# USB.net
KiCad netlist of a schematic drawn in Altium Designer
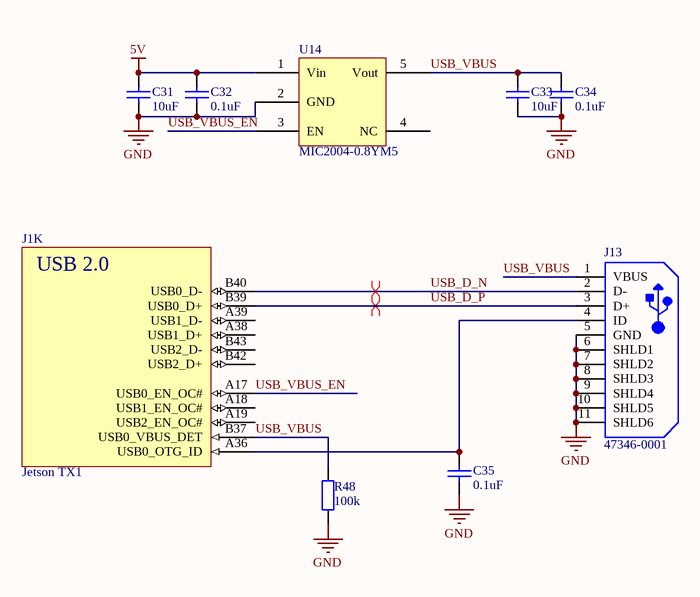
[diagram p0: USB.SchDoc]

(export (version "E")
  (design (tool "Eeschema 10.0.6"))
  (components
    (comp (ref "C31")
      (value "10uF")
      (footprint "0603C_M")
      (description "CAP CER 10UF 6.3V X5R 0603")
      (fields
        (field (name "MANUFACTURER") "Murata Electronics North America")
        (field (name "MANUFACTURER PART NUMBER") "GRM188R60J106ME47D")
      )
      (libsource (lib "KMTI-main") (part "GRM188R60J106ME47D"))
    )
    (comp (ref "C32")
      (value "GRM155R71C104KA88D")
      (footprint "0402C_M")
      (description "CAP CER 0.1UF 16V X7R 0402")
      (fields
        (field (name "MANUFACTURER") "Murata Electronics North America")
        (field (name "TOLERANCE") "±10%")
        (field (name "CAPACITANCE") "0.1uF")
      )
      (libsource (lib "KMTI-main") (part "GRM155R71C104KA88D"))
    )
    (comp (ref "C33")
      (value "10uF")
      (footprint "0603C_M")
      (description "CAP CER 10UF 6.3V X5R 0603")
      (fields
        (field (name "MANUFACTURER") "Murata Electronics North America")
        (field (name "MANUFACTURER PART NUMBER") "GRM188R60J106ME47D")
      )
      (libsource (lib "KMTI-main") (part "GRM188R60J106ME47D"))
    )
    (comp (ref "C34")
      (value "GRM155R71C104KA88D")
      (footprint "0402C_M")
      (description "CAP CER 0.1UF 16V X7R 0402")
      (fields
        (field (name "MANUFACTURER") "Murata Electronics North America")
        (field (name "TOLERANCE") "±10%")
        (field (name "CAPACITANCE") "0.1uF")
      )
      (libsource (lib "KMTI-main") (part "GRM155R71C104KA88D"))
    )
    (comp (ref "C35")
      (value "GRM155R71C104KA88D")
      (footprint "0402C_M")
      (description "CAP CER 0.1UF 16V X7R 0402")
      (fields
        (field (name "MANUFACTURER") "Murata Electronics North America")
        (field (name "TOLERANCE") "±10%")
        (field (name "CAPACITANCE") "0.1uF")
      )
      (libsource (lib "KMTI-main") (part "GRM155R71C104KA88D"))
    )
    (comp (ref "J1")
      (value "Jetson TX1")
      (footprint "Nvidia Jetson TX1")
      (description "Nvidia computing module")
      (libsource (lib "Modules") (part "NVIDIA_Jetson_TX1"))
    )
    (comp (ref "J13")
      (value "47346-0001")
      (footprint "MOLX-47346-0001-5_V")
      (description "Micro-USB B Receptacle with Flange, -30 to 85 degC, 5-Pin SMD, RoHS, Tape and Reel")
      (fields (field (name "MANUFACTURER") "Molex"))
      (libsource (lib "Altium Content Vault") (part "MOLX-47346-0001-5"))
    )
    (comp (ref "R48")
      (value "CRCW0402100KJNED")
      (footprint "0402R_M")
      (description "RES SMD 100K OHM 5% 1/16W 0402")
      (fields
        (field (name "MANUFACTURER") "Vishay")
        (field (name "TOLERANCE") "5 %")
        (field (name "RESISTANCE") "100k")
      )
      (libsource (lib "KMTI-main") (part "CRCW0402100KJNED"))
    )
    (comp (ref "U14")
      (value "MIC2004-0.8YM5")
      (footprint "SOT23_M5_L")
      (description "IC DISTRIBUTION SW 0.8A SOT23-5")
      (fields (field (name "MANUFACTURER") "Microchip Technology"))
      (libsource (lib "KMTI-main") (part "MIC2004-0.8YM5"))
    )
  )
  (nets
    (net (code "1") (name "/USB_D_N") (class "Default")
      (node (ref "J1") (pin "B40") (pinfunction "USB0_D-_B40") (pintype "bidirectional"))
      (node (ref "J13") (pin "2") (pinfunction "D-_2") (pintype "passive"))
    )
    (net (code "2") (name "/USB_D_P") (class "Default")
      (node (ref "J1") (pin "B39") (pinfunction "USB0_D+_B39") (pintype "bidirectional"))
      (node (ref "J13") (pin "3") (pinfunction "D+_3") (pintype "passive"))
    )
    (net (code "3") (name "/USB_VBUS") (class "Default")
      (node (ref "C33") (pin "2") (pinfunction "2_2") (pintype "passive"))
      (node (ref "C34") (pin "2") (pinfunction "2_2") (pintype "passive"))
      (node (ref "J1") (pin "B37") (pinfunction "USB0_VBUS_DET_B37") (pintype "input"))
      (node (ref "J13") (pin "1") (pinfunction "VBUS_1") (pintype "passive"))
      (node (ref "R48") (pin "2") (pinfunction "2_2") (pintype "passive"))
      (node (ref "U14") (pin "5") (pinfunction "Vout_5") (pintype "passive"))
    )
    (net (code "4") (name "/USB_VBUS_EN") (class "Default")
      (node (ref "J1") (pin "A17") (pinfunction "USB0_EN_OC#_A17") (pintype "bidirectional"))
      (node (ref "U14") (pin "3") (pinfunction "EN_3") (pintype "passive"))
    )
    (net (code "5") (name "5V") (class "Default")
      (node (ref "C31") (pin "2") (pinfunction "2_2") (pintype "passive"))
      (node (ref "C32") (pin "2") (pinfunction "2_2") (pintype "passive"))
      (node (ref "U14") (pin "1") (pinfunction "Vin_1") (pintype "passive"))
    )
    (net (code "6") (name "GND") (class "Default")
      (node (ref "C31") (pin "1") (pinfunction "1_1") (pintype "passive"))
      (node (ref "C32") (pin "1") (pinfunction "1_1") (pintype "passive"))
      (node (ref "C33") (pin "1") (pinfunction "1_1") (pintype "passive"))
      (node (ref "C34") (pin "1") (pinfunction "1_1") (pintype "passive"))
      (node (ref "C35") (pin "1") (pinfunction "1_1") (pintype "passive"))
      (node (ref "J13") (pin "10") (pinfunction "SHLD5_10") (pintype "passive"))
      (node (ref "J13") (pin "11") (pinfunction "SHLD6_11") (pintype "passive"))
      (node (ref "J13") (pin "5") (pinfunction "GND_5") (pintype "passive"))
      (node (ref "J13") (pin "6") (pinfunction "SHLD1_6") (pintype "passive"))
      (node (ref "J13") (pin "7") (pinfunction "SHLD2_7") (pintype "passive"))
      (node (ref "J13") (pin "8") (pinfunction "SHLD3_8") (pintype "passive"))
      (node (ref "J13") (pin "9") (pinfunction "SHLD4_9") (pintype "passive"))
      (node (ref "R48") (pin "1") (pinfunction "1_1") (pintype "passive"))
      (node (ref "U14") (pin "2") (pinfunction "GND_2") (pintype "passive"))
    )
    (net (code "7") (name "Net-(J13-ID)") (class "Default")
      (node (ref "C35") (pin "2") (pinfunction "2_2") (pintype "passive"))
      (node (ref "J1") (pin "A36") (pinfunction "USB0_OTG_ID_A36") (pintype "input"))
      (node (ref "J13") (pin "4") (pinfunction "ID_4") (pintype "passive"))
    )
    (net (code "8") (name "unconnected-(J1K-USB1_D+-PadA38)") (class "Default")
      (node (ref "J1") (pin "A38") (pinfunction "USB1_D+_A38") (pintype "bidirectional"))
    )
    (net (code "9") (name "unconnected-(J1K-USB1_D--PadA39)") (class "Default")
      (node (ref "J1") (pin "A39") (pinfunction "USB1_D-_A39") (pintype "bidirectional"))
    )
    (net (code "10") (name "unconnected-(J1K-USB1_EN_OC#-PadA18)") (class "Default")
      (node (ref "J1") (pin "A18") (pinfunction "USB1_EN_OC#_A18") (pintype "bidirectional"))
    )
    (net (code "11") (name "unconnected-(J1K-USB2_D+-PadB42)") (class "Default")
      (node (ref "J1") (pin "B42") (pinfunction "USB2_D+_B42") (pintype "bidirectional"))
    )
    (net (code "12") (name "unconnected-(J1K-USB2_D--PadB43)") (class "Default")
      (node (ref "J1") (pin "B43") (pinfunction "USB2_D-_B43") (pintype "bidirectional"))
    )
    (net (code "13") (name "unconnected-(J1K-USB2_EN_OC#-PadA19)") (class "Default")
      (node (ref "J1") (pin "A19") (pinfunction "USB2_EN_OC#_A19") (pintype "bidirectional"))
    )
    (net (code "14") (name "unconnected-(U14-NC-Pad4)") (class "Default")
      (node (ref "U14") (pin "4") (pinfunction "NC_4") (pintype "passive"))
    )
  )
)
